# power_5V.net
KiCad netlist of a schematic drawn in Altium Designer
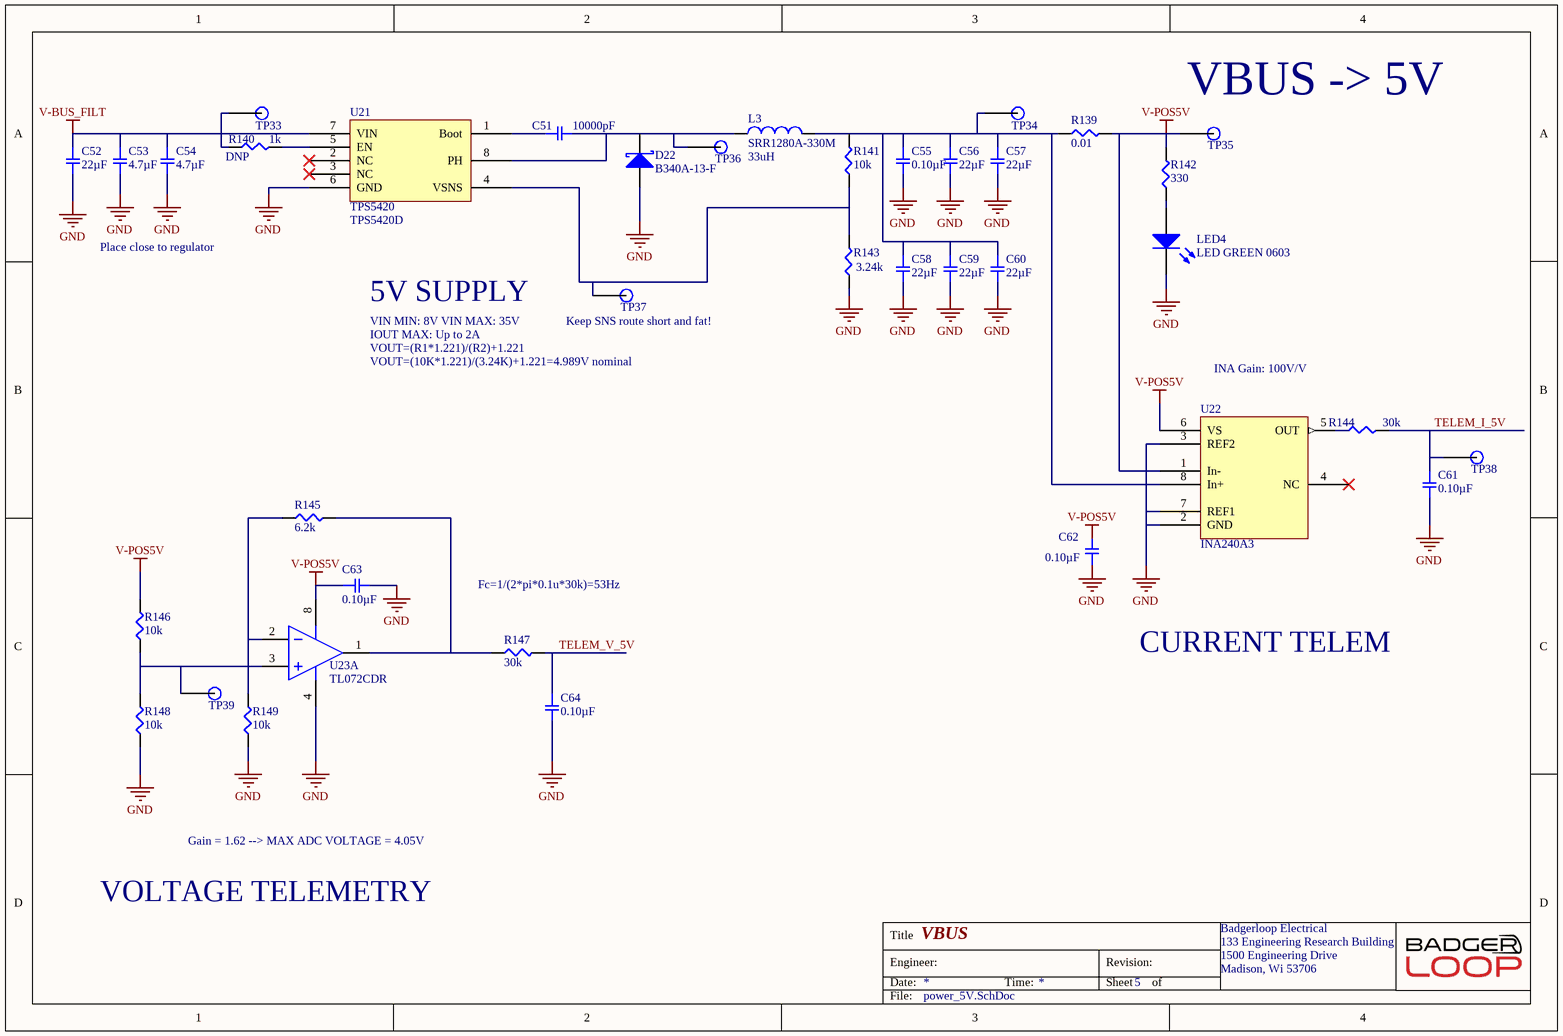
[diagram p0: power_5V.SchDoc]

(export (version "E")
  (design (tool "Eeschema 10.0.6"))
  (components
    (comp (ref "C51")
      (value "10000pF")
      (footprint "SMD-0805C")
      (description "CAP CER 10000PF 250V X7T 0805")
      (fields
        (field (name "DIGI-KEY PART NUMBER") "490-13986-1-ND")
        (field (name "PART NUMBER") "GC321AD72E103KX01D")
      )
      (libsource (lib "capacitors") (part "GC321AD72E103KX01D"))
    )
    (comp (ref "C52")
      (value "22µF")
      (footprint "SMD-1206C")
      (description "CAP CER 22UF 25V X5R 1206")
      (fields
        (field (name "DIGI-KEY PART NUMBER") "490-12451-1-ND")
        (field (name "PART NUMBER") "GRT31CR61E226ME01L")
      )
      (libsource (lib "capacitors") (part "GRT31CR61E226ME01L"))
    )
    (comp (ref "C53")
      (value "4.7µF")
      (footprint "SMD-1206C")
      (description "CAP CER 4.7UF 50V X7S 1206")
      (fields
        (field (name "DIGI-KEY PART NUMBER") "490-11167-1-ND")
        (field (name "PART NUMBER") "GCM31CC71H475KA03L")
      )
      (libsource (lib "capacitors") (part "GCM31CC71H475KA03L"))
    )
    (comp (ref "C54")
      (value "4.7µF")
      (footprint "SMD-1206C")
      (description "CAP CER 4.7UF 50V X7S 1206")
      (fields
        (field (name "DIGI-KEY PART NUMBER") "490-11167-1-ND")
        (field (name "PART NUMBER") "GCM31CC71H475KA03L")
      )
      (libsource (lib "capacitors") (part "GCM31CC71H475KA03L"))
    )
    (comp (ref "C55")
      (value "0.10µF")
      (footprint "SMD-0805C")
      (description "CAP CER 0.1UF 10V U2J 0805")
      (fields
        (field (name "DIGI-KEY PART NUMBER") "490-11592-1-ND")
        (field (name "PART NUMBER") "GRM21B7U1A104JA01L")
      )
      (libsource (lib "capacitors") (part "GRM21B7U1A104JA01L"))
    )
    (comp (ref "C56")
      (value "22µF")
      (footprint "SMD-1206C")
      (description "CAP CER 22UF 25V X5R 1206")
      (fields
        (field (name "DIGI-KEY PART NUMBER") "490-12451-1-ND")
        (field (name "PART NUMBER") "GRT31CR61E226ME01L")
      )
      (libsource (lib "capacitors") (part "GRT31CR61E226ME01L"))
    )
    (comp (ref "C57")
      (value "22µF")
      (footprint "SMD-1206C")
      (description "CAP CER 22UF 25V X5R 1206")
      (fields
        (field (name "DIGI-KEY PART NUMBER") "490-12451-1-ND")
        (field (name "PART NUMBER") "GRT31CR61E226ME01L")
      )
      (libsource (lib "capacitors") (part "GRT31CR61E226ME01L"))
    )
    (comp (ref "C58")
      (value "22µF")
      (footprint "SMD-1206C")
      (description "CAP CER 22UF 25V X5R 1206")
      (fields
        (field (name "DIGI-KEY PART NUMBER") "490-12451-1-ND")
        (field (name "PART NUMBER") "GRT31CR61E226ME01L")
      )
      (libsource (lib "capacitors") (part "GRT31CR61E226ME01L"))
    )
    (comp (ref "C59")
      (value "22µF")
      (footprint "SMD-1206C")
      (description "CAP CER 22UF 25V X5R 1206")
      (fields
        (field (name "DIGI-KEY PART NUMBER") "490-12451-1-ND")
        (field (name "PART NUMBER") "GRT31CR61E226ME01L")
      )
      (libsource (lib "capacitors") (part "GRT31CR61E226ME01L"))
    )
    (comp (ref "C60")
      (value "22µF")
      (footprint "SMD-1206C")
      (description "CAP CER 22UF 25V X5R 1206")
      (fields
        (field (name "DIGI-KEY PART NUMBER") "490-12451-1-ND")
        (field (name "PART NUMBER") "GRT31CR61E226ME01L")
      )
      (libsource (lib "capacitors") (part "GRT31CR61E226ME01L"))
    )
    (comp (ref "C61")
      (value "0.10µF")
      (footprint "SMD-0805C")
      (description "CAP CER 0.1UF 16V X7R 0805")
      (fields
        (field (name "DIGI-KEY PART NUMBER") "490-1683-1-ND")
        (field (name "PART NUMBER") "GRM219R71C104KA01D")
      )
      (libsource (lib "capacitors") (part "GRM219R71C104KA01D"))
    )
    (comp (ref "C62")
      (value "0.10µF")
      (footprint "SMD-0805C")
      (description "CAP CER 0.1UF 10V U2J 0805")
      (fields
        (field (name "DIGI-KEY PART NUMBER") "490-11592-1-ND")
        (field (name "PART NUMBER") "GRM21B7U1A104JA01L")
      )
      (libsource (lib "capacitors") (part "GRM21B7U1A104JA01L"))
    )
    (comp (ref "C63")
      (value "0.10µF")
      (footprint "SMD-0805C")
      (description "CAP CER 0.1UF 10V U2J 0805")
      (fields
        (field (name "DIGI-KEY PART NUMBER") "490-11592-1-ND")
        (field (name "PART NUMBER") "GRM21B7U1A104JA01L")
      )
      (libsource (lib "capacitors") (part "GRM21B7U1A104JA01L"))
    )
    (comp (ref "C64")
      (value "0.10µF")
      (footprint "SMD-0805C")
      (description "CAP CER 0.1UF 16V X7R 0805")
      (fields
        (field (name "DIGI-KEY PART NUMBER") "490-1683-1-ND")
        (field (name "PART NUMBER") "GRM219R71C104KA01D")
      )
      (libsource (lib "capacitors") (part "GRM219R71C104KA01D"))
    )
    (comp (ref "D22")
      (value "B340A-13-F")
      (footprint "DIOM4326X20N")
      (description "DIODE SCHOTTKY 40V 3A SMA")
      (fields (field (name "MANUFACTURER") "Diodes") (field (name "VOLTAGE") "40V"))
      (libsource (lib "misc") (part "B340A-13-F"))
    )
    (comp (ref "L3")
      (value "SRR1280A-330M")
      (footprint "INDM120125X75N")
      (description "Inductor Power Shielded Wirewound 33uH 20% 1KHz 28Q-Factor Ferrite 3.5A 57mOhm DCR Automotive T/R")
      (fields
        (field (name "MANUFACTURER") "Bourns")
        (field (name "TOLERANCE") "20%")
        (field (name "INDUCTANCE") "33uH")
      )
      (libsource (lib "inductor") (part "SRR1280A-330M"))
    )
    (comp (ref "LED4")
      (value "LED GREEN 0603")
      (footprint "LED 0603 GREEN")
      (fields (field (name "MANUFACTURER") "Lite-On Inc."))
      (libsource (lib "misc") (part "LED GREEN 0603"))
    )
    (comp (ref "R139")
      (value "0.01")
      (footprint "SMD-1206-RES")
      (description "RES SMD 0.01 OHM 1% 1/2W 1206")
      (fields
        (field (name "PART NUMBER") "ERJ-MP2KF10MU")
        (field (name "DIGI-KEY PART NUMBER") "P19322CT-ND")
      )
      (libsource (lib "resistors") (part "ERJ-MP2KF10MU"))
    )
    (comp (ref "R140")
      (value "1k")
      (footprint "SMD-0805-RES")
      (description "RES SMD 1K OHM 5% 1/2W 0805")
      (fields
        (field (name "PART NUMBER") "ERJ-P06J102V")
        (field (name "DIGI-KEY PART NUMBER") "P1.0KADCT-ND")
        (field (name "DNP") "DNP")
      )
      (libsource (lib "resistors") (part "ERJ-P06J102V"))
    )
    (comp (ref "R141")
      (value "10k")
      (footprint "SMD-0805-RES")
      (description "RES SMD 10K OHM 5% 1/2W 0805")
      (fields (field (name "PART NUMBER") "ERJ-P06J103V") (field (name "DIGI-KEY PART NUMBER") "P10KADCT-ND"))
      (libsource (lib "resistors") (part "ERJ-P06J103V"))
    )
    (comp (ref "R142")
      (value "330")
      (footprint "SMD-0805-RES")
      (description "RES SMD 330 OHM 5% 1/2W 0805")
      (fields (field (name "PART NUMBER") "ERJ-P06J331V") (field (name "DIGI-KEY PART NUMBER") "P330ADCT-ND"))
      (libsource (lib "resistors") (part "ERJ-P06J331V"))
    )
    (comp (ref "R143")
      (value "3.24k")
      (footprint "SMD-0805-RES")
      (description "RES SMD 3.24K OHM 1% 1/8W 0805")
      (fields
        (field (name "PART NUMBER") "ERJ-6ENF3241V")
        (field (name "DIGI-KEY PART NUMBER") "P3.24KCCT-ND")
      )
      (libsource (lib "resistors") (part "ERJ-6ENF3241V"))
    )
    (comp (ref "R144")
      (value "30k")
      (footprint "SMD-0805-RES")
      (description "RES SMD 30K OHM 1% 1/8W 0805")
      (fields
        (field (name "PART NUMBER") "ERJ-6ENF3002V")
        (field (name "DIGI-KEY PART NUMBER") "P30.0KCCT-ND")
      )
      (libsource (lib "resistors") (part "ERJ-6ENF3002V"))
    )
    (comp (ref "R145")
      (value "6.2k")
      (footprint "SMD-0805-RES")
      (description "RES SMD 6.2K OHM 5% 1/2W 0805")
      (fields
        (field (name "PART NUMBER") "ERJ-P06J622V")
        (field (name "DIGI-KEY PART NUMBER") "P6.2KADCT-ND")
      )
      (libsource (lib "resistors") (part "ERJ-P06J622V"))
    )
    (comp (ref "R146")
      (value "10k")
      (footprint "SMD-0805-RES")
      (description "RES SMD 10K OHM 5% 1/2W 0805")
      (fields (field (name "PART NUMBER") "ERJ-P06J103V") (field (name "DIGI-KEY PART NUMBER") "P10KADCT-ND"))
      (libsource (lib "resistors") (part "ERJ-P06J103V"))
    )
    (comp (ref "R147")
      (value "30k")
      (footprint "SMD-0805-RES")
      (description "RES SMD 30K OHM 5% 1/2W 0805")
      (fields (field (name "PART NUMBER") "ERJ-P06J303V") (field (name "DIGI-KEY PART NUMBER") "P30KADCT-ND"))
      (libsource (lib "resistors") (part "ERJ-P06J303V"))
    )
    (comp (ref "R148")
      (value "10k")
      (footprint "SMD-0805-RES")
      (description "RES SMD 10K OHM 5% 1/2W 0805")
      (fields (field (name "PART NUMBER") "ERJ-P06J103V") (field (name "DIGI-KEY PART NUMBER") "P10KADCT-ND"))
      (libsource (lib "resistors") (part "ERJ-P06J103V"))
    )
    (comp (ref "R149")
      (value "10k")
      (footprint "SMD-0805-RES")
      (description "RES SMD 10K OHM 5% 1/2W 0805")
      (fields (field (name "PART NUMBER") "ERJ-P06J103V") (field (name "DIGI-KEY PART NUMBER") "P10KADCT-ND"))
      (libsource (lib "resistors") (part "ERJ-P06J103V"))
    )
    (comp (ref "TP33")
      (value "TP")
      (footprint "Test Point")
      (description "SMD TEST POINT")
      (libsource (lib "misc") (part "TP"))
    )
    (comp (ref "TP34")
      (value "TP")
      (footprint "Test Point")
      (description "SMD TEST POINT")
      (libsource (lib "misc") (part "TP"))
    )
    (comp (ref "TP35")
      (value "TP")
      (footprint "Test Point")
      (description "SMD TEST POINT")
      (libsource (lib "misc") (part "TP"))
    )
    (comp (ref "TP36")
      (value "TP")
      (footprint "Test Point")
      (description "SMD TEST POINT")
      (libsource (lib "misc") (part "TP"))
    )
    (comp (ref "TP37")
      (value "TP")
      (footprint "Test Point")
      (description "SMD TEST POINT")
      (libsource (lib "misc") (part "TP"))
    )
    (comp (ref "TP38")
      (value "TP")
      (footprint "Test Point")
      (description "SMD TEST POINT")
      (libsource (lib "misc") (part "TP"))
    )
    (comp (ref "TP39")
      (value "TP")
      (footprint "Test Point")
      (description "SMD TEST POINT")
      (libsource (lib "misc") (part "TP"))
    )
    (comp (ref "U21")
      (value "TPS5420")
      (footprint "SOP127P600X175-8N")
      (fields
        (field (name "MANUFACTURER") "Texas Instruments")
        (field (name "MANUFACTURER PART NUMBER") "TPS5420D")
      )
      (libsource (lib "ic") (part "TPS5420"))
    )
    (comp (ref "U22")
      (value "INA240A3")
      (footprint "SOIC127P600X175-8N")
      (description "IC AMP CURRENT SENSE 8-TSSOP 100V/V")
      (fields (field (name "MANUFACTURER") "Texas Instruments"))
      (libsource (lib "ic") (part "INA240A3"))
    )
    (comp (ref "U23")
      (value "TL072CDR")
      (footprint "SOP127P600X175-8N")
      (description "IC OPAMP JFET 3MHZ 8SOIC")
      (fields (field (name "MANUFACTURER") "Texas Instruments"))
      (libsource (lib "ic") (part "TL072CDR"))
    )
  )
  (nets
    (net (code "1") (name "/TELEM_I_5V") (class "Default")
      (node (ref "C61") (pin "1") (pinfunction "1_1") (pintype "passive"))
      (node (ref "R144") (pin "2") (pinfunction "2_2") (pintype "passive"))
      (node (ref "TP38") (pin "1") (pinfunction "1_1") (pintype "passive"))
    )
    (net (code "2") (name "/TELEM_V_5V") (class "Default")
      (node (ref "C64") (pin "1") (pinfunction "1_1") (pintype "passive"))
      (node (ref "R147") (pin "2") (pinfunction "2_2") (pintype "passive"))
    )
    (net (code "3") (name "GND") (class "Default")
      (node (ref "C52") (pin "2") (pinfunction "2_2") (pintype "passive"))
      (node (ref "C53") (pin "2") (pinfunction "2_2") (pintype "passive"))
      (node (ref "C54") (pin "2") (pinfunction "2_2") (pintype "passive"))
      (node (ref "C55") (pin "2") (pinfunction "2_2") (pintype "passive"))
      (node (ref "C56") (pin "2") (pinfunction "2_2") (pintype "passive"))
      (node (ref "C57") (pin "2") (pinfunction "2_2") (pintype "passive"))
      (node (ref "C58") (pin "2") (pinfunction "2_2") (pintype "passive"))
      (node (ref "C59") (pin "2") (pinfunction "2_2") (pintype "passive"))
      (node (ref "C60") (pin "2") (pinfunction "2_2") (pintype "passive"))
      (node (ref "C61") (pin "2") (pinfunction "2_2") (pintype "passive"))
      (node (ref "C62") (pin "1") (pinfunction "1_1") (pintype "passive"))
      (node (ref "C63") (pin "2") (pinfunction "2_2") (pintype "passive"))
      (node (ref "C64") (pin "2") (pinfunction "2_2") (pintype "passive"))
      (node (ref "D22") (pin "2") (pinfunction "A_2") (pintype "passive"))
      (node (ref "LED4") (pin "2") (pinfunction "K_2") (pintype "passive"))
      (node (ref "R143") (pin "1") (pinfunction "1_1") (pintype "passive"))
      (node (ref "R148") (pin "1") (pinfunction "1_1") (pintype "passive"))
      (node (ref "R149") (pin "1") (pinfunction "1_1") (pintype "passive"))
      (node (ref "U21") (pin "6") (pinfunction "GND_6") (pintype "passive"))
      (node (ref "U22") (pin "2") (pinfunction "GND_2") (pintype "power_in"))
      (node (ref "U22") (pin "3") (pinfunction "REF2_3") (pintype "passive"))
      (node (ref "U22") (pin "7") (pinfunction "REF1_7") (pintype "passive"))
      (node (ref "U23") (pin "4") (pinfunction "V-_4") (pintype "power_in"))
    )
    (net (code "4") (name "Net-(D22-K)") (class "Default")
      (node (ref "C51") (pin "2") (pinfunction "2_2") (pintype "passive"))
      (node (ref "D22") (pin "1") (pinfunction "K_1") (pintype "passive"))
      (node (ref "L3") (pin "1") (pinfunction "1_1") (pintype "passive"))
      (node (ref "TP36") (pin "1") (pinfunction "1_1") (pintype "passive"))
      (node (ref "U21") (pin "8") (pinfunction "PH_8") (pintype "passive"))
    )
    (net (code "5") (name "Net-(LED4-A)") (class "Default")
      (node (ref "LED4") (pin "1") (pinfunction "A_1") (pintype "passive"))
      (node (ref "R142") (pin "1") (pinfunction "1_1") (pintype "passive"))
    )
    (net (code "6") (name "Net-(U21-Boot)") (class "Default")
      (node (ref "C51") (pin "1") (pinfunction "1_1") (pintype "passive"))
      (node (ref "U21") (pin "1") (pinfunction "Boot_1") (pintype "passive"))
    )
    (net (code "7") (name "Net-(U21-EN)") (class "Default")
      (node (ref "R140") (pin "2") (pinfunction "2_2") (pintype "passive"))
      (node (ref "U21") (pin "5") (pinfunction "EN_5") (pintype "passive"))
    )
    (net (code "8") (name "Net-(U21-VSNS)") (class "Default")
      (node (ref "R141") (pin "1") (pinfunction "1_1") (pintype "passive"))
      (node (ref "R143") (pin "2") (pinfunction "2_2") (pintype "passive"))
      (node (ref "TP37") (pin "1") (pinfunction "1_1") (pintype "passive"))
      (node (ref "U21") (pin "4") (pinfunction "VSNS_4") (pintype "power_in"))
    )
    (net (code "9") (name "Net-(U22-In+)") (class "Default")
      (node (ref "C55") (pin "1") (pinfunction "1_1") (pintype "passive"))
      (node (ref "C56") (pin "1") (pinfunction "1_1") (pintype "passive"))
      (node (ref "C57") (pin "1") (pinfunction "1_1") (pintype "passive"))
      (node (ref "C58") (pin "1") (pinfunction "1_1") (pintype "passive"))
      (node (ref "C59") (pin "1") (pinfunction "1_1") (pintype "passive"))
      (node (ref "C60") (pin "1") (pinfunction "1_1") (pintype "passive"))
      (node (ref "L3") (pin "2") (pinfunction "2_2") (pintype "passive"))
      (node (ref "R139") (pin "1") (pinfunction "1_1") (pintype "passive"))
      (node (ref "R141") (pin "2") (pinfunction "2_2") (pintype "passive"))
      (node (ref "TP34") (pin "1") (pinfunction "1_1") (pintype "passive"))
      (node (ref "U22") (pin "8") (pinfunction "In+_8") (pintype "passive"))
    )
    (net (code "10") (name "Net-(U22-OUT)") (class "Default")
      (node (ref "R144") (pin "1") (pinfunction "1_1") (pintype "passive"))
      (node (ref "U22") (pin "5") (pinfunction "OUT_5") (pintype "output"))
    )
    (net (code "11") (name "Net-(U23A-IN+)") (class "Default")
      (node (ref "R146") (pin "1") (pinfunction "1_1") (pintype "passive"))
      (node (ref "R148") (pin "2") (pinfunction "2_2") (pintype "passive"))
      (node (ref "TP39") (pin "1") (pinfunction "1_1") (pintype "passive"))
      (node (ref "U23") (pin "3") (pinfunction "IN+_3") (pintype "passive"))
    )
    (net (code "12") (name "Net-(U23A-IN-)") (class "Default")
      (node (ref "R145") (pin "1") (pinfunction "1_1") (pintype "passive"))
      (node (ref "R149") (pin "2") (pinfunction "2_2") (pintype "passive"))
      (node (ref "U23") (pin "2") (pinfunction "IN-_2") (pintype "passive"))
    )
    (net (code "13") (name "Net-(U23A-OUT)") (class "Default")
      (node (ref "R145") (pin "2") (pinfunction "2_2") (pintype "passive"))
      (node (ref "R147") (pin "1") (pinfunction "1_1") (pintype "passive"))
      (node (ref "U23") (pin "1") (pinfunction "OUT_1") (pintype "passive"))
    )
    (net (code "14") (name "V-BUS_FILT") (class "Default")
      (node (ref "C52") (pin "1") (pinfunction "1_1") (pintype "passive"))
      (node (ref "C53") (pin "1") (pinfunction "1_1") (pintype "passive"))
      (node (ref "C54") (pin "1") (pinfunction "1_1") (pintype "passive"))
      (node (ref "R140") (pin "1") (pinfunction "1_1") (pintype "passive"))
      (node (ref "TP33") (pin "1") (pinfunction "1_1") (pintype "passive"))
      (node (ref "U21") (pin "7") (pinfunction "VIN_7") (pintype "passive"))
    )
    (net (code "15") (name "V-POS5V") (class "Default")
      (node (ref "C62") (pin "2") (pinfunction "2_2") (pintype "passive"))
      (node (ref "C63") (pin "1") (pinfunction "1_1") (pintype "passive"))
      (node (ref "R139") (pin "2") (pinfunction "2_2") (pintype "passive"))
      (node (ref "R142") (pin "2") (pinfunction "2_2") (pintype "passive"))
      (node (ref "R146") (pin "2") (pinfunction "2_2") (pintype "passive"))
      (node (ref "TP35") (pin "1") (pinfunction "1_1") (pintype "passive"))
      (node (ref "U22") (pin "1") (pinfunction "In-_1") (pintype "passive"))
      (node (ref "U22") (pin "6") (pinfunction "VS_6") (pintype "power_in"))
      (node (ref "U23") (pin "8") (pinfunction "V+_8") (pintype "power_in"))
    )
    (net (code "16") (name "unconnected-(U21-NC-Pad2)") (class "Default")
      (node (ref "U21") (pin "2") (pinfunction "NC_2") (pintype "power_in+no_connect"))
    )
    (net (code "17") (name "unconnected-(U21-NC-Pad3)") (class "Default")
      (node (ref "U21") (pin "3") (pinfunction "NC_3") (pintype "passive+no_connect"))
    )
    (net (code "18") (name "unconnected-(U22-NC-Pad4)") (class "Default")
      (node (ref "U22") (pin "4") (pinfunction "NC_4") (pintype "passive+no_connect"))
    )
  )
)
